# e-Tapperhandpiece16.net
KiCad netlist of a schematic drawn in EAGLE
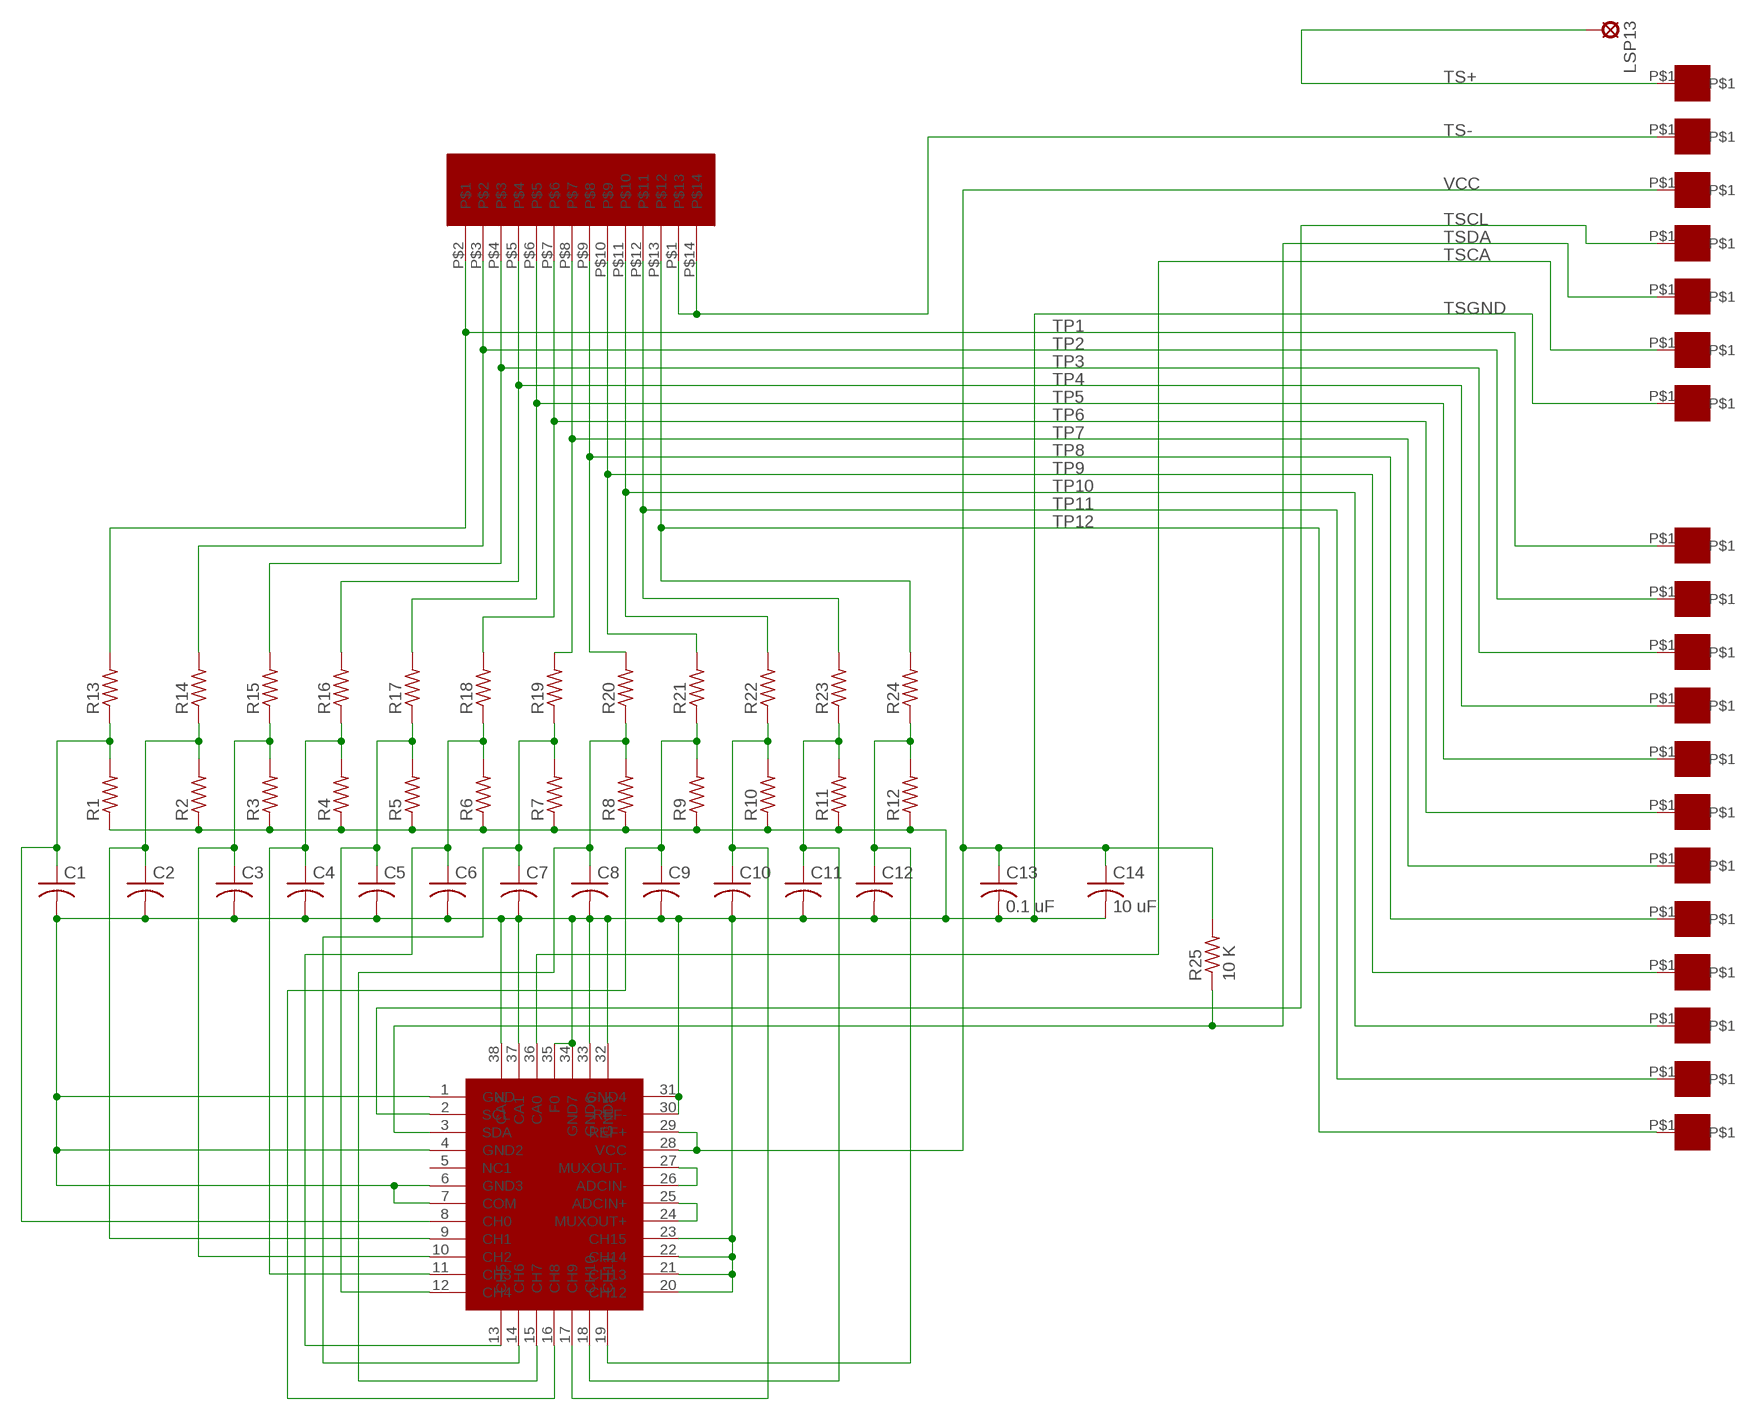
[diagram p0: schematic, sheet 1]

(export (version "E")
  (design (tool "Eeschema 10.0.6"))
  (components
    (comp (ref "C1")
      (value "C-USC0603")
      (footprint "eagle-import:C0603")
      (libsource (lib "eagle-import") (part "C-USC0603"))
    )
    (comp (ref "C2")
      (value "C-USC0603")
      (footprint "eagle-import:C0603")
      (libsource (lib "eagle-import") (part "C-USC0603"))
    )
    (comp (ref "C3")
      (value "C-USC0603")
      (footprint "eagle-import:C0603")
      (libsource (lib "eagle-import") (part "C-USC0603"))
    )
    (comp (ref "C4")
      (value "C-USC0603")
      (footprint "eagle-import:C0603")
      (libsource (lib "eagle-import") (part "C-USC0603"))
    )
    (comp (ref "C5")
      (value "C-USC0603")
      (footprint "eagle-import:C0603")
      (libsource (lib "eagle-import") (part "C-USC0603"))
    )
    (comp (ref "C6")
      (value "C-USC0603")
      (footprint "eagle-import:C0603")
      (libsource (lib "eagle-import") (part "C-USC0603"))
    )
    (comp (ref "C7")
      (value "C-USC0603")
      (footprint "eagle-import:C0603")
      (libsource (lib "eagle-import") (part "C-USC0603"))
    )
    (comp (ref "C8")
      (value "C-USC0603")
      (footprint "eagle-import:C0603")
      (libsource (lib "eagle-import") (part "C-USC0603"))
    )
    (comp (ref "C9")
      (value "C-USC0603")
      (footprint "eagle-import:C0603")
      (libsource (lib "eagle-import") (part "C-USC0603"))
    )
    (comp (ref "C10")
      (value "C-USC0603")
      (footprint "eagle-import:C0603")
      (libsource (lib "eagle-import") (part "C-USC0603"))
    )
    (comp (ref "C11")
      (value "C-USC0603")
      (footprint "eagle-import:C0603")
      (libsource (lib "eagle-import") (part "C-USC0603"))
    )
    (comp (ref "C12")
      (value "C-USC0603")
      (footprint "eagle-import:C0603")
      (libsource (lib "eagle-import") (part "C-USC0603"))
    )
    (comp (ref "C13")
      (value "0.1 uF")
      (footprint "eagle-import:C0603")
      (libsource (lib "eagle-import") (part "C-USC0603"))
    )
    (comp (ref "C14")
      (value "10 uF")
      (footprint "eagle-import:C0805")
      (libsource (lib "eagle-import") (part "C-USC0805"))
    )
    (comp (ref "LSP13")
      (value "SE11")
      (footprint "eagle-import:SE11")
      (libsource (lib "eagle-import") (part "SE11"))
    )
    (comp (ref "R1")
      (value "R-US_R0402")
      (footprint "eagle-import:R0402")
      (libsource (lib "eagle-import") (part "R-US_R0402"))
    )
    (comp (ref "R2")
      (value "R-US_R0402")
      (footprint "eagle-import:R0402")
      (libsource (lib "eagle-import") (part "R-US_R0402"))
    )
    (comp (ref "R3")
      (value "R-US_R0402")
      (footprint "eagle-import:R0402")
      (libsource (lib "eagle-import") (part "R-US_R0402"))
    )
    (comp (ref "R4")
      (value "R-US_R0402")
      (footprint "eagle-import:R0402")
      (libsource (lib "eagle-import") (part "R-US_R0402"))
    )
    (comp (ref "R5")
      (value "R-US_R0402")
      (footprint "eagle-import:R0402")
      (libsource (lib "eagle-import") (part "R-US_R0402"))
    )
    (comp (ref "R6")
      (value "R-US_R0402")
      (footprint "eagle-import:R0402")
      (libsource (lib "eagle-import") (part "R-US_R0402"))
    )
    (comp (ref "R7")
      (value "R-US_R0402")
      (footprint "eagle-import:R0402")
      (libsource (lib "eagle-import") (part "R-US_R0402"))
    )
    (comp (ref "R8")
      (value "R-US_R0402")
      (footprint "eagle-import:R0402")
      (libsource (lib "eagle-import") (part "R-US_R0402"))
    )
    (comp (ref "R9")
      (value "R-US_R0402")
      (footprint "eagle-import:R0402")
      (libsource (lib "eagle-import") (part "R-US_R0402"))
    )
    (comp (ref "R10")
      (value "R-US_R0402")
      (footprint "eagle-import:R0402")
      (libsource (lib "eagle-import") (part "R-US_R0402"))
    )
    (comp (ref "R11")
      (value "R-US_R0402")
      (footprint "eagle-import:R0402")
      (libsource (lib "eagle-import") (part "R-US_R0402"))
    )
    (comp (ref "R12")
      (value "R-US_R0402")
      (footprint "eagle-import:R0402")
      (libsource (lib "eagle-import") (part "R-US_R0402"))
    )
    (comp (ref "R13")
      (value "R-US_R0402")
      (footprint "eagle-import:R0402")
      (libsource (lib "eagle-import") (part "R-US_R0402"))
    )
    (comp (ref "R14")
      (value "R-US_R0402")
      (footprint "eagle-import:R0402")
      (libsource (lib "eagle-import") (part "R-US_R0402"))
    )
    (comp (ref "R15")
      (value "R-US_R0402")
      (footprint "eagle-import:R0402")
      (libsource (lib "eagle-import") (part "R-US_R0402"))
    )
    (comp (ref "R16")
      (value "R-US_R0402")
      (footprint "eagle-import:R0402")
      (libsource (lib "eagle-import") (part "R-US_R0402"))
    )
    (comp (ref "R17")
      (value "R-US_R0402")
      (footprint "eagle-import:R0402")
      (libsource (lib "eagle-import") (part "R-US_R0402"))
    )
    (comp (ref "R18")
      (value "R-US_R0402")
      (footprint "eagle-import:R0402")
      (libsource (lib "eagle-import") (part "R-US_R0402"))
    )
    (comp (ref "R19")
      (value "R-US_R0402")
      (footprint "eagle-import:R0402")
      (libsource (lib "eagle-import") (part "R-US_R0402"))
    )
    (comp (ref "R20")
      (value "R-US_R0402")
      (footprint "eagle-import:R0402")
      (libsource (lib "eagle-import") (part "R-US_R0402"))
    )
    (comp (ref "R21")
      (value "R-US_R0402")
      (footprint "eagle-import:R0402")
      (libsource (lib "eagle-import") (part "R-US_R0402"))
    )
    (comp (ref "R22")
      (value "R-US_R0402")
      (footprint "eagle-import:R0402")
      (libsource (lib "eagle-import") (part "R-US_R0402"))
    )
    (comp (ref "R23")
      (value "R-US_R0402")
      (footprint "eagle-import:R0402")
      (libsource (lib "eagle-import") (part "R-US_R0402"))
    )
    (comp (ref "R24")
      (value "R-US_R0402")
      (footprint "eagle-import:R0402")
      (libsource (lib "eagle-import") (part "R-US_R0402"))
    )
    (comp (ref "R25")
      (value "10 K")
      (footprint "eagle-import:R0402")
      (libsource (lib "eagle-import") (part "R-US_R0402"))
    )
    (comp (ref "TSP1")
      (value "ET1")
      (footprint "eagle-import:ET1")
      (libsource (lib "eagle-import") (part "ET1"))
    )
    (comp (ref "TSP2")
      (value "ET1")
      (footprint "eagle-import:ET1")
      (libsource (lib "eagle-import") (part "ET1"))
    )
    (comp (ref "TSP3")
      (value "ET1")
      (footprint "eagle-import:ET1")
      (libsource (lib "eagle-import") (part "ET1"))
    )
    (comp (ref "TSP4")
      (value "ET1")
      (footprint "eagle-import:ET1")
      (libsource (lib "eagle-import") (part "ET1"))
    )
    (comp (ref "TSP5")
      (value "ET1")
      (footprint "eagle-import:ET1")
      (libsource (lib "eagle-import") (part "ET1"))
    )
    (comp (ref "TSP6")
      (value "ET1")
      (footprint "eagle-import:ET1")
      (libsource (lib "eagle-import") (part "ET1"))
    )
    (comp (ref "TSP7")
      (value "ET1")
      (footprint "eagle-import:ET1")
      (libsource (lib "eagle-import") (part "ET1"))
    )
    (comp (ref "TSP8")
      (value "ET1")
      (footprint "eagle-import:ET1")
      (libsource (lib "eagle-import") (part "ET1"))
    )
    (comp (ref "TSP9")
      (value "ET1")
      (footprint "eagle-import:ET1")
      (libsource (lib "eagle-import") (part "ET1"))
    )
    (comp (ref "TSP10")
      (value "ET1")
      (footprint "eagle-import:ET1")
      (libsource (lib "eagle-import") (part "ET1"))
    )
    (comp (ref "TSP11")
      (value "ET1")
      (footprint "eagle-import:ET1")
      (libsource (lib "eagle-import") (part "ET1"))
    )
    (comp (ref "TSP12")
      (value "ET1")
      (footprint "eagle-import:ET1")
      (libsource (lib "eagle-import") (part "ET1"))
    )
    (comp (ref "TSP13")
      (value "ET1")
      (footprint "eagle-import:ET1")
      (libsource (lib "eagle-import") (part "ET1"))
    )
    (comp (ref "TSP14")
      (value "ET1")
      (footprint "eagle-import:ET1")
      (libsource (lib "eagle-import") (part "ET1"))
    )
    (comp (ref "TSP15")
      (value "ET1")
      (footprint "eagle-import:ET1")
      (libsource (lib "eagle-import") (part "ET1"))
    )
    (comp (ref "TSP16")
      (value "ET1")
      (footprint "eagle-import:ET1")
      (libsource (lib "eagle-import") (part "ET1"))
    )
    (comp (ref "TSP17")
      (value "ET1")
      (footprint "eagle-import:ET1")
      (libsource (lib "eagle-import") (part "ET1"))
    )
    (comp (ref "TSP18")
      (value "ET1")
      (footprint "eagle-import:ET1")
      (libsource (lib "eagle-import") (part "ET1"))
    )
    (comp (ref "TSP19")
      (value "ET1")
      (footprint "eagle-import:ET1")
      (libsource (lib "eagle-import") (part "ET1"))
    )
    (comp (ref "U$1")
      (value "LTC2497")
      (footprint "eagle-import:QFN38-5X7")
      (libsource (lib "eagle-import") (part "LTC2497"))
    )
    (comp (ref "U$2")
      (value "SS112D01")
      (footprint "eagle-import:SS112D01")
      (libsource (lib "eagle-import") (part "SS112D01"))
    )
  )
  (nets
    (net (code "1") (name "/TP1") (class "Default")
      (node (ref "R13") (pin "2") (pinfunction "2_2") (pintype "passive"))
      (node (ref "TSP1") (pin "P$1") (pinfunction "P$1_P$1") (pintype "bidirectional"))
      (node (ref "U$2") (pin "P$2") (pinfunction "P$1_P$2") (pintype "bidirectional"))
    )
    (net (code "2") (name "/TP2") (class "Default")
      (node (ref "R14") (pin "2") (pinfunction "2_2") (pintype "passive"))
      (node (ref "TSP2") (pin "P$1") (pinfunction "P$1_P$1") (pintype "bidirectional"))
      (node (ref "U$2") (pin "P$3") (pinfunction "P$2_P$3") (pintype "bidirectional"))
    )
    (net (code "3") (name "/TP3") (class "Default")
      (node (ref "R15") (pin "2") (pinfunction "2_2") (pintype "passive"))
      (node (ref "TSP3") (pin "P$1") (pinfunction "P$1_P$1") (pintype "bidirectional"))
      (node (ref "U$2") (pin "P$4") (pinfunction "P$3_P$4") (pintype "bidirectional"))
    )
    (net (code "4") (name "/TP4") (class "Default")
      (node (ref "R16") (pin "2") (pinfunction "2_2") (pintype "passive"))
      (node (ref "TSP4") (pin "P$1") (pinfunction "P$1_P$1") (pintype "bidirectional"))
      (node (ref "U$2") (pin "P$5") (pinfunction "P$4_P$5") (pintype "bidirectional"))
    )
    (net (code "5") (name "/TP5") (class "Default")
      (node (ref "R17") (pin "2") (pinfunction "2_2") (pintype "passive"))
      (node (ref "TSP5") (pin "P$1") (pinfunction "P$1_P$1") (pintype "bidirectional"))
      (node (ref "U$2") (pin "P$6") (pinfunction "P$5_P$6") (pintype "bidirectional"))
    )
    (net (code "6") (name "/TP6") (class "Default")
      (node (ref "R18") (pin "2") (pinfunction "2_2") (pintype "passive"))
      (node (ref "TSP6") (pin "P$1") (pinfunction "P$1_P$1") (pintype "bidirectional"))
      (node (ref "U$2") (pin "P$7") (pinfunction "P$6_P$7") (pintype "bidirectional"))
    )
    (net (code "7") (name "/TP7") (class "Default")
      (node (ref "R19") (pin "2") (pinfunction "2_2") (pintype "passive"))
      (node (ref "TSP7") (pin "P$1") (pinfunction "P$1_P$1") (pintype "bidirectional"))
      (node (ref "U$2") (pin "P$8") (pinfunction "P$7_P$8") (pintype "bidirectional"))
    )
    (net (code "8") (name "/TP8") (class "Default")
      (node (ref "R20") (pin "2") (pinfunction "2_2") (pintype "passive"))
      (node (ref "TSP8") (pin "P$1") (pinfunction "P$1_P$1") (pintype "bidirectional"))
      (node (ref "U$2") (pin "P$9") (pinfunction "P$8_P$9") (pintype "bidirectional"))
    )
    (net (code "9") (name "/TP9") (class "Default")
      (node (ref "R21") (pin "2") (pinfunction "2_2") (pintype "passive"))
      (node (ref "TSP9") (pin "P$1") (pinfunction "P$1_P$1") (pintype "bidirectional"))
      (node (ref "U$2") (pin "P$10") (pinfunction "P$9_P$10") (pintype "bidirectional"))
    )
    (net (code "10") (name "/TP10") (class "Default")
      (node (ref "R22") (pin "2") (pinfunction "2_2") (pintype "passive"))
      (node (ref "TSP10") (pin "P$1") (pinfunction "P$1_P$1") (pintype "bidirectional"))
      (node (ref "U$2") (pin "P$11") (pinfunction "P$10_P$11") (pintype "bidirectional"))
    )
    (net (code "11") (name "/TP11") (class "Default")
      (node (ref "R23") (pin "2") (pinfunction "2_2") (pintype "passive"))
      (node (ref "TSP11") (pin "P$1") (pinfunction "P$1_P$1") (pintype "bidirectional"))
      (node (ref "U$2") (pin "P$12") (pinfunction "P$11_P$12") (pintype "bidirectional"))
    )
    (net (code "12") (name "/TP12") (class "Default")
      (node (ref "R24") (pin "2") (pinfunction "2_2") (pintype "passive"))
      (node (ref "TSP12") (pin "P$1") (pinfunction "P$1_P$1") (pintype "bidirectional"))
      (node (ref "U$2") (pin "P$13") (pinfunction "P$12_P$13") (pintype "bidirectional"))
    )
    (net (code "13") (name "/TS+") (class "Default")
      (node (ref "LSP13") (pin "MP") (pinfunction "MP_MP") (pintype "passive"))
      (node (ref "TSP13") (pin "P$1") (pinfunction "P$1_P$1") (pintype "bidirectional"))
    )
    (net (code "14") (name "/TS-") (class "Default")
      (node (ref "TSP14") (pin "P$1") (pinfunction "P$1_P$1") (pintype "bidirectional"))
      (node (ref "U$2") (pin "P$1") (pinfunction "P$13_P$1") (pintype "bidirectional"))
      (node (ref "U$2") (pin "P$14") (pinfunction "P$14_P$14") (pintype "bidirectional"))
    )
    (net (code "15") (name "/TSCA") (class "Default")
      (node (ref "TSP18") (pin "P$1") (pinfunction "P$1_P$1") (pintype "bidirectional"))
      (node (ref "U$1") (pin "36") (pinfunction "CA0_36") (pintype "bidirectional"))
    )
    (net (code "16") (name "/TSCL") (class "Default")
      (node (ref "TSP16") (pin "P$1") (pinfunction "P$1_P$1") (pintype "bidirectional"))
      (node (ref "U$1") (pin "2") (pinfunction "SCL_2") (pintype "bidirectional"))
    )
    (net (code "17") (name "/TSDA") (class "Default")
      (node (ref "R25") (pin "1") (pinfunction "1_1") (pintype "passive"))
      (node (ref "TSP17") (pin "P$1") (pinfunction "P$1_P$1") (pintype "bidirectional"))
      (node (ref "U$1") (pin "3") (pinfunction "SDA_3") (pintype "bidirectional"))
    )
    (net (code "18") (name "/TSGND") (class "Default")
      (node (ref "C1") (pin "2") (pinfunction "2_2") (pintype "passive"))
      (node (ref "C10") (pin "2") (pinfunction "2_2") (pintype "passive"))
      (node (ref "C11") (pin "2") (pinfunction "2_2") (pintype "passive"))
      (node (ref "C12") (pin "2") (pinfunction "2_2") (pintype "passive"))
      (node (ref "C13") (pin "2") (pinfunction "2_2") (pintype "passive"))
      (node (ref "C14") (pin "2") (pinfunction "2_2") (pintype "passive"))
      (node (ref "C2") (pin "2") (pinfunction "2_2") (pintype "passive"))
      (node (ref "C3") (pin "2") (pinfunction "2_2") (pintype "passive"))
      (node (ref "C4") (pin "2") (pinfunction "2_2") (pintype "passive"))
      (node (ref "C5") (pin "2") (pinfunction "2_2") (pintype "passive"))
      (node (ref "C6") (pin "2") (pinfunction "2_2") (pintype "passive"))
      (node (ref "C7") (pin "2") (pinfunction "2_2") (pintype "passive"))
      (node (ref "C8") (pin "2") (pinfunction "2_2") (pintype "passive"))
      (node (ref "C9") (pin "2") (pinfunction "2_2") (pintype "passive"))
      (node (ref "R1") (pin "1") (pinfunction "1_1") (pintype "passive"))
      (node (ref "R10") (pin "1") (pinfunction "1_1") (pintype "passive"))
      (node (ref "R11") (pin "1") (pinfunction "1_1") (pintype "passive"))
      (node (ref "R12") (pin "1") (pinfunction "1_1") (pintype "passive"))
      (node (ref "R2") (pin "1") (pinfunction "1_1") (pintype "passive"))
      (node (ref "R3") (pin "1") (pinfunction "1_1") (pintype "passive"))
      (node (ref "R4") (pin "1") (pinfunction "1_1") (pintype "passive"))
      (node (ref "R5") (pin "1") (pinfunction "1_1") (pintype "passive"))
      (node (ref "R6") (pin "1") (pinfunction "1_1") (pintype "passive"))
      (node (ref "R7") (pin "1") (pinfunction "1_1") (pintype "passive"))
      (node (ref "R8") (pin "1") (pinfunction "1_1") (pintype "passive"))
      (node (ref "R9") (pin "1") (pinfunction "1_1") (pintype "passive"))
      (node (ref "TSP19") (pin "P$1") (pinfunction "P$1_P$1") (pintype "bidirectional"))
      (node (ref "U$1") (pin "1") (pinfunction "GND_1") (pintype "power_in"))
      (node (ref "U$1") (pin "20") (pinfunction "CH12_20") (pintype "input"))
      (node (ref "U$1") (pin "21") (pinfunction "CH13_21") (pintype "input"))
      (node (ref "U$1") (pin "22") (pinfunction "CH14_22") (pintype "input"))
      (node (ref "U$1") (pin "23") (pinfunction "CH15_23") (pintype "input"))
      (node (ref "U$1") (pin "30") (pinfunction "REF-_30") (pintype "bidirectional"))
      (node (ref "U$1") (pin "31") (pinfunction "GND4_31") (pintype "power_in"))
      (node (ref "U$1") (pin "32") (pinfunction "GND5_32") (pintype "power_in"))
      (node (ref "U$1") (pin "33") (pinfunction "GND6_33") (pintype "power_in"))
      (node (ref "U$1") (pin "34") (pinfunction "GND7_34") (pintype "power_in"))
      (node (ref "U$1") (pin "35") (pinfunction "F0_35") (pintype "bidirectional"))
      (node (ref "U$1") (pin "37") (pinfunction "CA1_37") (pintype "bidirectional"))
      (node (ref "U$1") (pin "38") (pinfunction "CA2_38") (pintype "bidirectional"))
      (node (ref "U$1") (pin "4") (pinfunction "GND2_4") (pintype "power_in"))
      (node (ref "U$1") (pin "6") (pinfunction "GND3_6") (pintype "power_in"))
      (node (ref "U$1") (pin "7") (pinfunction "COM_7") (pintype "power_in"))
    )
    (net (code "19") (name "/VCC") (class "Default")
      (node (ref "C13") (pin "1") (pinfunction "1_1") (pintype "passive"))
      (node (ref "C14") (pin "1") (pinfunction "1_1") (pintype "passive"))
      (node (ref "R25") (pin "2") (pinfunction "2_2") (pintype "passive"))
      (node (ref "TSP15") (pin "P$1") (pinfunction "P$1_P$1") (pintype "bidirectional"))
      (node (ref "U$1") (pin "28") (pinfunction "VCC_28") (pintype "power_in"))
      (node (ref "U$1") (pin "29") (pinfunction "REF+_29") (pintype "bidirectional"))
    )
    (net (code "20") (name "Net-(U$1-ADCIN+)") (class "Default")
      (node (ref "U$1") (pin "24") (pinfunction "MUXOUT+_24") (pintype "bidirectional"))
      (node (ref "U$1") (pin "25") (pinfunction "ADCIN+_25") (pintype "bidirectional"))
    )
    (net (code "21") (name "Net-(U$1-ADCIN-)") (class "Default")
      (node (ref "U$1") (pin "26") (pinfunction "ADCIN-_26") (pintype "bidirectional"))
      (node (ref "U$1") (pin "27") (pinfunction "MUXOUT-_27") (pintype "bidirectional"))
    )
    (net (code "22") (name "Net-(U$1-CH0)") (class "Default")
      (node (ref "C1") (pin "1") (pinfunction "1_1") (pintype "passive"))
      (node (ref "R1") (pin "2") (pinfunction "2_2") (pintype "passive"))
      (node (ref "R13") (pin "1") (pinfunction "1_1") (pintype "passive"))
      (node (ref "U$1") (pin "8") (pinfunction "CH0_8") (pintype "input"))
    )
    (net (code "23") (name "Net-(U$1-CH1)") (class "Default")
      (node (ref "C2") (pin "1") (pinfunction "1_1") (pintype "passive"))
      (node (ref "R14") (pin "1") (pinfunction "1_1") (pintype "passive"))
      (node (ref "R2") (pin "2") (pinfunction "2_2") (pintype "passive"))
      (node (ref "U$1") (pin "9") (pinfunction "CH1_9") (pintype "input"))
    )
    (net (code "24") (name "Net-(U$1-CH2)") (class "Default")
      (node (ref "C3") (pin "1") (pinfunction "1_1") (pintype "passive"))
      (node (ref "R15") (pin "1") (pinfunction "1_1") (pintype "passive"))
      (node (ref "R3") (pin "2") (pinfunction "2_2") (pintype "passive"))
      (node (ref "U$1") (pin "10") (pinfunction "CH2_10") (pintype "input"))
    )
    (net (code "25") (name "Net-(U$1-CH3)") (class "Default")
      (node (ref "C4") (pin "1") (pinfunction "1_1") (pintype "passive"))
      (node (ref "R16") (pin "1") (pinfunction "1_1") (pintype "passive"))
      (node (ref "R4") (pin "2") (pinfunction "2_2") (pintype "passive"))
      (node (ref "U$1") (pin "11") (pinfunction "CH3_11") (pintype "input"))
    )
    (net (code "26") (name "Net-(U$1-CH4)") (class "Default")
      (node (ref "C5") (pin "1") (pinfunction "1_1") (pintype "passive"))
      (node (ref "R17") (pin "1") (pinfunction "1_1") (pintype "passive"))
      (node (ref "R5") (pin "2") (pinfunction "2_2") (pintype "passive"))
      (node (ref "U$1") (pin "12") (pinfunction "CH4_12") (pintype "input"))
    )
    (net (code "27") (name "Net-(U$1-CH5)") (class "Default")
      (node (ref "C6") (pin "1") (pinfunction "1_1") (pintype "passive"))
      (node (ref "R18") (pin "1") (pinfunction "1_1") (pintype "passive"))
      (node (ref "R6") (pin "2") (pinfunction "2_2") (pintype "passive"))
      (node (ref "U$1") (pin "13") (pinfunction "CH5_13") (pintype "input"))
    )
    (net (code "28") (name "Net-(U$1-CH6)") (class "Default")
      (node (ref "C7") (pin "1") (pinfunction "1_1") (pintype "passive"))
      (node (ref "R19") (pin "1") (pinfunction "1_1") (pintype "passive"))
      (node (ref "R7") (pin "2") (pinfunction "2_2") (pintype "passive"))
      (node (ref "U$1") (pin "14") (pinfunction "CH6_14") (pintype "input"))
    )
    (net (code "29") (name "Net-(U$1-CH7)") (class "Default")
      (node (ref "C8") (pin "1") (pinfunction "1_1") (pintype "passive"))
      (node (ref "R20") (pin "1") (pinfunction "1_1") (pintype "passive"))
      (node (ref "R8") (pin "2") (pinfunction "2_2") (pintype "passive"))
      (node (ref "U$1") (pin "15") (pinfunction "CH7_15") (pintype "input"))
    )
    (net (code "30") (name "Net-(U$1-CH8)") (class "Default")
      (node (ref "C9") (pin "1") (pinfunction "1_1") (pintype "passive"))
      (node (ref "R21") (pin "1") (pinfunction "1_1") (pintype "passive"))
      (node (ref "R9") (pin "2") (pinfunction "2_2") (pintype "passive"))
      (node (ref "U$1") (pin "16") (pinfunction "CH8_16") (pintype "input"))
    )
    (net (code "31") (name "Net-(U$1-CH9)") (class "Default")
      (node (ref "C10") (pin "1") (pinfunction "1_1") (pintype "passive"))
      (node (ref "R10") (pin "2") (pinfunction "2_2") (pintype "passive"))
      (node (ref "R22") (pin "1") (pinfunction "1_1") (pintype "passive"))
      (node (ref "U$1") (pin "17") (pinfunction "CH9_17") (pintype "input"))
    )
    (net (code "32") (name "Net-(U$1-CH10)") (class "Default")
      (node (ref "C11") (pin "1") (pinfunction "1_1") (pintype "passive"))
      (node (ref "R11") (pin "2") (pinfunction "2_2") (pintype "passive"))
      (node (ref "R23") (pin "1") (pinfunction "1_1") (pintype "passive"))
      (node (ref "U$1") (pin "18") (pinfunction "CH10_18") (pintype "input"))
    )
    (net (code "33") (name "Net-(U$1-CH11)") (class "Default")
      (node (ref "C12") (pin "1") (pinfunction "1_1") (pintype "passive"))
      (node (ref "R12") (pin "2") (pinfunction "2_2") (pintype "passive"))
      (node (ref "R24") (pin "1") (pinfunction "1_1") (pintype "passive"))
      (node (ref "U$1") (pin "19") (pinfunction "CH11_19") (pintype "input"))
    )
    (net (code "34") (name "unconnected-(U$1-NC1-Pad5)") (class "Default")
      (node (ref "U$1") (pin "5") (pinfunction "NC1_5") (pintype "no_connect"))
    )
  )
)
